# audiostick.net
KiCad netlist of a schematic drawn in EAGLE
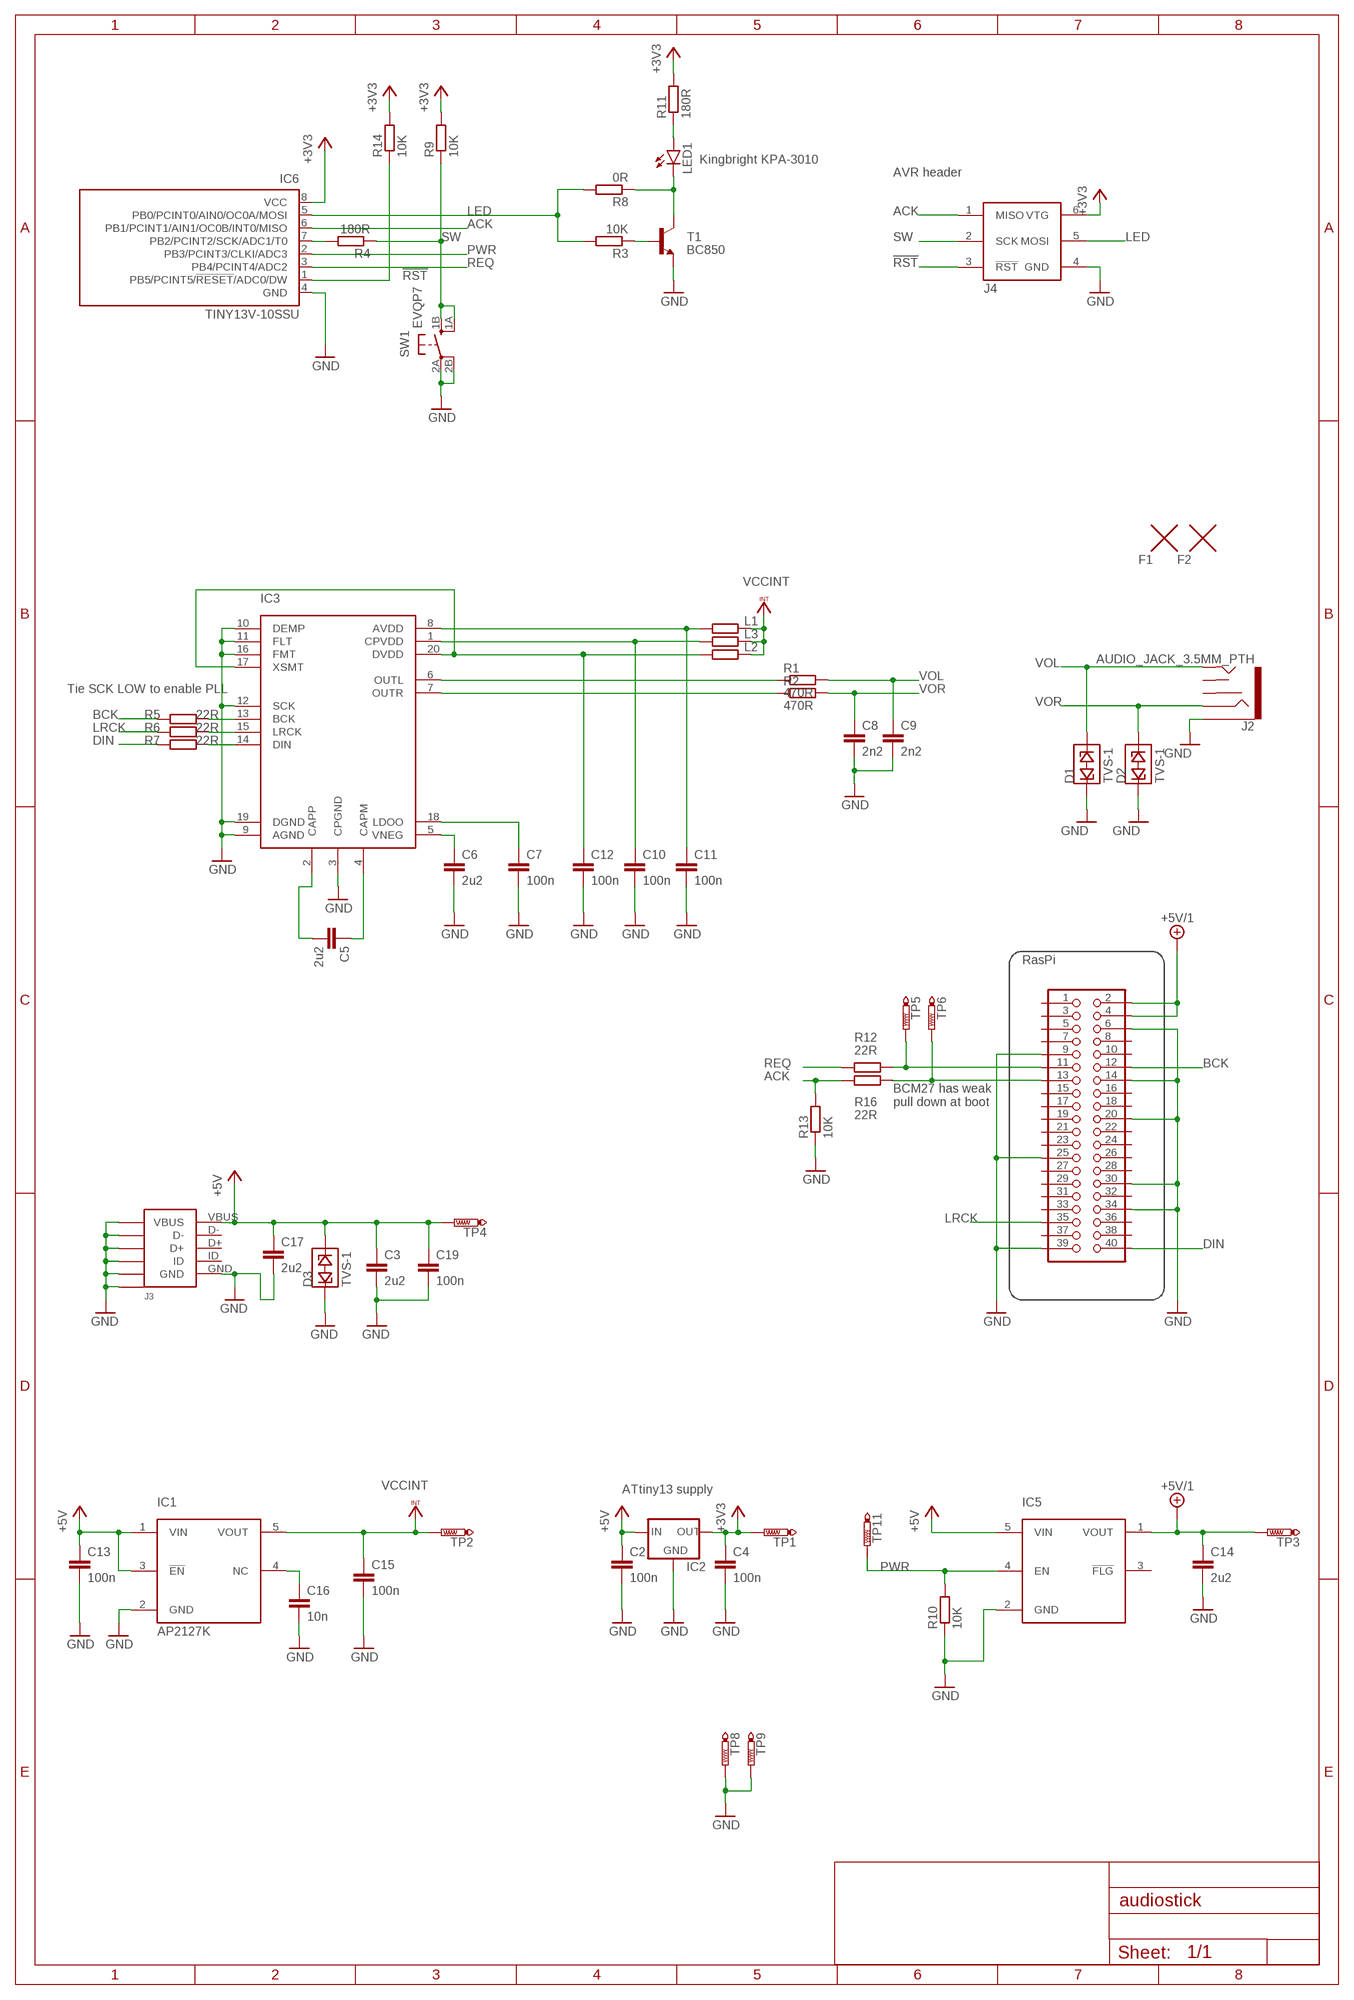
[diagram p0: schematic, sheet 1]

(export (version "E")
  (design (tool "Eeschema 10.0.6"))
  (components
    (comp (ref "C2")
      (value "100n")
      (footprint "eagle-import:C0603")
      (libsource (lib "eagle-import") (part "C-EUC0603"))
    )
    (comp (ref "C3")
      (value "2u2")
      (footprint "eagle-import:C0603")
      (libsource (lib "eagle-import") (part "C-EUC0603"))
    )
    (comp (ref "C4")
      (value "100n")
      (footprint "eagle-import:C0603")
      (libsource (lib "eagle-import") (part "C-EUC0603"))
    )
    (comp (ref "C5")
      (value "2u2")
      (footprint "eagle-import:C0603")
      (libsource (lib "eagle-import") (part "C-EUC0603"))
    )
    (comp (ref "C6")
      (value "2u2")
      (footprint "eagle-import:C0603")
      (libsource (lib "eagle-import") (part "C-EUC0603"))
    )
    (comp (ref "C7")
      (value "100n")
      (footprint "eagle-import:C0603")
      (libsource (lib "eagle-import") (part "C-EUC0603"))
    )
    (comp (ref "C8")
      (value "2n2")
      (footprint "eagle-import:C0603")
      (libsource (lib "eagle-import") (part "C-EUC0603"))
    )
    (comp (ref "C9")
      (value "2n2")
      (footprint "eagle-import:C0603")
      (libsource (lib "eagle-import") (part "C-EUC0603"))
    )
    (comp (ref "C10")
      (value "100n")
      (footprint "eagle-import:C0603")
      (libsource (lib "eagle-import") (part "C-EUC0603"))
    )
    (comp (ref "C11")
      (value "100n")
      (footprint "eagle-import:C0603")
      (libsource (lib "eagle-import") (part "C-EUC0603"))
    )
    (comp (ref "C12")
      (value "100n")
      (footprint "eagle-import:C0603")
      (libsource (lib "eagle-import") (part "C-EUC0603"))
    )
    (comp (ref "C13")
      (value "100n")
      (footprint "eagle-import:C0603")
      (libsource (lib "eagle-import") (part "C-EUC0603"))
    )
    (comp (ref "C14")
      (value "2u2")
      (footprint "eagle-import:C0603")
      (libsource (lib "eagle-import") (part "C-EUC0603"))
    )
    (comp (ref "C15")
      (value "100n")
      (footprint "eagle-import:C0603")
      (libsource (lib "eagle-import") (part "C-EUC0603"))
    )
    (comp (ref "C16")
      (value "10n")
      (footprint "eagle-import:C0603")
      (libsource (lib "eagle-import") (part "C-EUC0603"))
    )
    (comp (ref "C17")
      (value "2u2")
      (footprint "eagle-import:C0603")
      (libsource (lib "eagle-import") (part "C-EUC0603"))
    )
    (comp (ref "C19")
      (value "100n")
      (footprint "eagle-import:C0603")
      (libsource (lib "eagle-import") (part "C-EUC0603"))
    )
    (comp (ref "D1")
      (value "TVS-1")
      (footprint "eagle-import:R0603")
      (libsource (lib "eagle-import") (part "TVS-1"))
    )
    (comp (ref "D2")
      (value "TVS-1")
      (footprint "eagle-import:R0603")
      (libsource (lib "eagle-import") (part "TVS-1"))
    )
    (comp (ref "D3")
      (value "TVS-1")
      (footprint "eagle-import:R0603")
      (libsource (lib "eagle-import") (part "TVS-1"))
    )
    (comp (ref "F1")
      (value "FIDUCIALC2")
      (footprint "eagle-import:CIRCLE-1MM-3R")
      (libsource (lib "eagle-import") (part "FIDUCIALC2"))
    )
    (comp (ref "F2")
      (value "FIDUCIALC2")
      (footprint "eagle-import:CIRCLE-1MM-3R")
      (libsource (lib "eagle-import") (part "FIDUCIALC2"))
    )
    (comp (ref "IC1")
      (value "AP2127K")
      (footprint "eagle-import:GHI_SOT23-5")
      (libsource (lib "eagle-import") (part "AP2127K"))
    )
    (comp (ref "IC2")
      (value "MCP1700TT")
      (footprint "eagle-import:SOT-23")
      (libsource (lib "eagle-import") (part "MCP1700TT"))
    )
    (comp (ref "IC3")
      (value "PCM5102ASW")
      (footprint "eagle-import:TSSOP20")
      (libsource (lib "eagle-import") (part "PCM5102ASW"))
    )
    (comp (ref "IC5")
      (value "AP22804W5")
      (footprint "eagle-import:GHI_SOT23-5")
      (libsource (lib "eagle-import") (part "AP22804W5"))
    )
    (comp (ref "IC6")
      (value "TINY13V-10SSU")
      (footprint "eagle-import:8S1")
      (fields (field (name "MPN") "ATTINY13V-10SSU"))
      (libsource (lib "eagle-import") (part "TINY13SSUV-10"))
    )
    (comp (ref "J2")
      (value "AUDIO_JACK_3.5MM_PTH")
      (footprint "eagle-import:AUDIO-JACK")
      (libsource (lib "eagle-import") (part "AUDIO_JACK_3.5MM_PTH"))
    )
    (comp (ref "J3")
      (value "USB-B")
      (footprint "eagle-import:1050170001")
      (libsource (lib "eagle-import") (part "USB-B"))
    )
    (comp (ref "J4")
      (value "AVRISP")
      (footprint "eagle-import:2X3-1.27")
      (libsource (lib "eagle-import") (part "AVRISP"))
    )
    (comp (ref "L1")
      (value "F")
      (footprint "eagle-import:R0603")
      (libsource (lib "eagle-import") (part "R-EU_R0603"))
    )
    (comp (ref "L2")
      (value "F")
      (footprint "eagle-import:R0603")
      (libsource (lib "eagle-import") (part "R-EU_R0603"))
    )
    (comp (ref "L3")
      (value "F")
      (footprint "eagle-import:R0603")
      (libsource (lib "eagle-import") (part "R-EU_R0603"))
    )
    (comp (ref "LED1")
      (value "LEDLED")
      (footprint "eagle-import:KPA-3010")
      (libsource (lib "eagle-import") (part "LEDLED"))
    )
    (comp (ref "R1")
      (value "470R")
      (footprint "eagle-import:R0603")
      (libsource (lib "eagle-import") (part "R-EU_R0603"))
    )
    (comp (ref "R2")
      (value "470R")
      (footprint "eagle-import:R0603")
      (libsource (lib "eagle-import") (part "R-EU_R0603"))
    )
    (comp (ref "R3")
      (value "10K")
      (footprint "eagle-import:R0603")
      (libsource (lib "eagle-import") (part "R-EU_R0603"))
    )
    (comp (ref "R4")
      (value "180R")
      (footprint "eagle-import:R0603")
      (libsource (lib "eagle-import") (part "R-EU_R0603"))
    )
    (comp (ref "R5")
      (value "22R")
      (footprint "eagle-import:R0603")
      (libsource (lib "eagle-import") (part "R-EU_R0603"))
    )
    (comp (ref "R6")
      (value "22R")
      (footprint "eagle-import:R0603")
      (libsource (lib "eagle-import") (part "R-EU_R0603"))
    )
    (comp (ref "R7")
      (value "22R")
      (footprint "eagle-import:R0603")
      (libsource (lib "eagle-import") (part "R-EU_R0603"))
    )
    (comp (ref "R8")
      (value "0R")
      (footprint "eagle-import:R0603")
      (libsource (lib "eagle-import") (part "R-EU_R0603"))
    )
    (comp (ref "R9")
      (value "10K")
      (footprint "eagle-import:R0603")
      (libsource (lib "eagle-import") (part "R-EU_R0603"))
    )
    (comp (ref "R10")
      (value "10K")
      (footprint "eagle-import:R0603")
      (libsource (lib "eagle-import") (part "R-EU_R0603"))
    )
    (comp (ref "R11")
      (value "180R")
      (footprint "eagle-import:R0603")
      (libsource (lib "eagle-import") (part "R-EU_R0603"))
    )
    (comp (ref "R12")
      (value "22R")
      (footprint "eagle-import:R0603")
      (libsource (lib "eagle-import") (part "R-EU_R0603"))
    )
    (comp (ref "R13")
      (value "10K")
      (footprint "eagle-import:R0603")
      (libsource (lib "eagle-import") (part "R-EU_R0603"))
    )
    (comp (ref "R14")
      (value "10K")
      (footprint "eagle-import:R0603")
      (libsource (lib "eagle-import") (part "R-EU_R0603"))
    )
    (comp (ref "R16")
      (value "22R")
      (footprint "eagle-import:R0603")
      (libsource (lib "eagle-import") (part "R-EU_R0603"))
    )
    (comp (ref "SW1")
      (value "EVQP7")
      (footprint "eagle-import:EVQP7L")
      (libsource (lib "eagle-import") (part "EVQP7"))
    )
    (comp (ref "T1")
      (value "BC850")
      (footprint "eagle-import:SOT23")
      (libsource (lib "eagle-import") (part "BC850"))
    )
    (comp (ref "TP1")
      (value "PTR1PAD1-13")
      (footprint "eagle-import:P1-13")
      (libsource (lib "eagle-import") (part "PTR1PAD1-13"))
    )
    (comp (ref "TP2")
      (value "PTR1PAD1-13")
      (footprint "eagle-import:P1-13")
      (libsource (lib "eagle-import") (part "PTR1PAD1-13"))
    )
    (comp (ref "TP3")
      (value "PTR1PAD1-13")
      (footprint "eagle-import:P1-13")
      (libsource (lib "eagle-import") (part "PTR1PAD1-13"))
    )
    (comp (ref "TP4")
      (value "PTR1PAD1-13")
      (footprint "eagle-import:P1-13")
      (libsource (lib "eagle-import") (part "PTR1PAD1-13"))
    )
    (comp (ref "TP5")
      (value "PTR1PAD1-13")
      (footprint "eagle-import:P1-13")
      (libsource (lib "eagle-import") (part "PTR1PAD1-13"))
    )
    (comp (ref "TP6")
      (value "PTR1PAD1-13")
      (footprint "eagle-import:P1-13")
      (libsource (lib "eagle-import") (part "PTR1PAD1-13"))
    )
    (comp (ref "TP8")
      (value "PTR1PAD1-13")
      (footprint "eagle-import:P1-13")
      (libsource (lib "eagle-import") (part "PTR1PAD1-13"))
    )
    (comp (ref "TP9")
      (value "PTR1PAD1-13")
      (footprint "eagle-import:P1-13")
      (libsource (lib "eagle-import") (part "PTR1PAD1-13"))
    )
    (comp (ref "TP11")
      (value "PTR1PAD1-13")
      (footprint "eagle-import:P1-13")
      (libsource (lib "eagle-import") (part "PTR1PAD1-13"))
    )
    (comp (ref "U$1")
      (value "RASPIZERO")
      (footprint "eagle-import:RASPIZERO")
      (libsource (lib "eagle-import") (part "RASPIZERO"))
    )
  )
  (nets
    (net (code "1") (name "+3V3") (class "Default")
      (node (ref "C4") (pin "1") (pinfunction "1_1") (pintype "passive"))
      (node (ref "IC2") (pin "2") (pinfunction "OUT_2") (pintype "passive"))
      (node (ref "IC6") (pin "8") (pinfunction "VCC_8") (pintype "power_in"))
      (node (ref "J4") (pin "6") (pinfunction "VTG_6") (pintype "bidirectional"))
      (node (ref "R11") (pin "2") (pinfunction "2_2") (pintype "passive"))
      (node (ref "R14") (pin "2") (pinfunction "2_2") (pintype "passive"))
      (node (ref "R9") (pin "2") (pinfunction "2_2") (pintype "passive"))
      (node (ref "TP1") (pin "TP") (pinfunction "TP_TP") (pintype "input"))
    )
    (net (code "2") (name "+5V") (class "Default")
      (node (ref "C13") (pin "1") (pinfunction "1_1") (pintype "passive"))
      (node (ref "C17") (pin "1") (pinfunction "1_1") (pintype "passive"))
      (node (ref "C19") (pin "1") (pinfunction "1_1") (pintype "passive"))
      (node (ref "C2") (pin "1") (pinfunction "1_1") (pintype "passive"))
      (node (ref "C3") (pin "1") (pinfunction "1_1") (pintype "passive"))
      (node (ref "D3") (pin "2") (pinfunction "3_2") (pintype "passive"))
      (node (ref "IC1") (pin "1") (pinfunction "VIN_1") (pintype "power_in"))
      (node (ref "IC1") (pin "3") (pinfunction "~{EN}_3") (pintype "input"))
      (node (ref "IC2") (pin "3") (pinfunction "IN_3") (pintype "input"))
      (node (ref "IC5") (pin "5") (pinfunction "VIN_5") (pintype "power_in"))
      (node (ref "J3") (pin "VBUS") (pinfunction "VBUS_VBUS") (pintype "power_in"))
      (node (ref "TP4") (pin "TP") (pinfunction "TP_TP") (pintype "input"))
    )
    (net (code "3") (name "+5V{slash}1") (class "Default")
      (node (ref "C14") (pin "1") (pinfunction "1_1") (pintype "passive"))
      (node (ref "IC5") (pin "1") (pinfunction "VOUT_1") (pintype "power_in"))
      (node (ref "TP3") (pin "TP") (pinfunction "TP_TP") (pintype "input"))
      (node (ref "U$1") (pin "2") (pinfunction "5V_2") (pintype "passive"))
      (node (ref "U$1") (pin "4") (pinfunction "5V_4") (pintype "passive"))
    )
    (net (code "4") (name "/ACK") (class "Default")
      (node (ref "IC6") (pin "6") (pinfunction "PB1/PCINT1/AIN1/OC0B/INT0/MISO_6") (pintype "bidirectional"))
      (node (ref "J4") (pin "1") (pinfunction "MISO_1") (pintype "bidirectional"))
      (node (ref "R13") (pin "2") (pinfunction "2_2") (pintype "passive"))
      (node (ref "R16") (pin "1") (pinfunction "1_1") (pintype "passive"))
    )
    (net (code "5") (name "/BCK") (class "Default")
      (node (ref "R5") (pin "1") (pinfunction "1_1") (pintype "passive"))
      (node (ref "U$1") (pin "12") (pinfunction "18_12") (pintype "passive"))
    )
    (net (code "6") (name "/DIN") (class "Default")
      (node (ref "R7") (pin "1") (pinfunction "1_1") (pintype "passive"))
      (node (ref "U$1") (pin "40") (pinfunction "21_40") (pintype "passive"))
    )
    (net (code "7") (name "/LED") (class "Default")
      (node (ref "IC6") (pin "5") (pinfunction "PB0/PCINT0/AIN0/OC0A/MOSI_5") (pintype "bidirectional"))
      (node (ref "J4") (pin "5") (pinfunction "MOSI_5") (pintype "bidirectional"))
      (node (ref "R3") (pin "2") (pinfunction "2_2") (pintype "passive"))
      (node (ref "R8") (pin "2") (pinfunction "2_2") (pintype "passive"))
    )
    (net (code "8") (name "/LRCK") (class "Default")
      (node (ref "R6") (pin "1") (pinfunction "1_1") (pintype "passive"))
      (node (ref "U$1") (pin "35") (pinfunction "19_35") (pintype "passive"))
    )
    (net (code "9") (name "/PWR") (class "Default")
      (node (ref "IC5") (pin "4") (pinfunction "EN_4") (pintype "input"))
      (node (ref "IC6") (pin "2") (pinfunction "PB3/PCINT3/CLKI/ADC3_2") (pintype "bidirectional"))
      (node (ref "R10") (pin "2") (pinfunction "2_2") (pintype "passive"))
      (node (ref "TP11") (pin "TP") (pinfunction "TP_TP") (pintype "input"))
    )
    (net (code "10") (name "/REQ") (class "Default")
      (node (ref "IC6") (pin "3") (pinfunction "PB4/PCINT4/ADC2_3") (pintype "bidirectional"))
      (node (ref "R12") (pin "1") (pinfunction "1_1") (pintype "passive"))
    )
    (net (code "11") (name "/SW") (class "Default")
      (node (ref "J4") (pin "2") (pinfunction "SCK_2") (pintype "bidirectional"))
      (node (ref "R4") (pin "1") (pinfunction "1_1") (pintype "passive"))
      (node (ref "R9") (pin "1") (pinfunction "1_1") (pintype "passive"))
      (node (ref "SW1") (pin "1A") (pinfunction "S1_1A") (pintype "passive"))
      (node (ref "SW1") (pin "1B") (pinfunction "S_1B") (pintype "passive"))
    )
    (net (code "12") (name "/VOL") (class "Default")
      (node (ref "C9") (pin "1") (pinfunction "1_1") (pintype "passive"))
      (node (ref "D1") (pin "2") (pinfunction "3_2") (pintype "passive"))
      (node (ref "J2") (pin "TIP") (pinfunction "TIP_TIP") (pintype "bidirectional"))
      (node (ref "R1") (pin "2") (pinfunction "2_2") (pintype "passive"))
    )
    (net (code "13") (name "/VOR") (class "Default")
      (node (ref "C8") (pin "1") (pinfunction "1_1") (pintype "passive"))
      (node (ref "D2") (pin "2") (pinfunction "3_2") (pintype "passive"))
      (node (ref "J2") (pin "RING") (pinfunction "RING_RING") (pintype "bidirectional"))
      (node (ref "R2") (pin "2") (pinfunction "2_2") (pintype "passive"))
    )
    (net (code "14") (name "/~{RST}") (class "Default")
      (node (ref "IC6") (pin "1") (pinfunction "PB5/PCINT5/~{RESET}/ADC0/DW_1") (pintype "bidirectional"))
      (node (ref "J4") (pin "3") (pinfunction "~{RST}_3") (pintype "bidirectional"))
      (node (ref "R14") (pin "1") (pinfunction "1_1") (pintype "passive"))
    )
    (net (code "15") (name "GND") (class "Default")
      (node (ref "C10") (pin "2") (pinfunction "2_2") (pintype "passive"))
      (node (ref "C11") (pin "2") (pinfunction "2_2") (pintype "passive"))
      (node (ref "C12") (pin "2") (pinfunction "2_2") (pintype "passive"))
      (node (ref "C13") (pin "2") (pinfunction "2_2") (pintype "passive"))
      (node (ref "C14") (pin "2") (pinfunction "2_2") (pintype "passive"))
      (node (ref "C15") (pin "2") (pinfunction "2_2") (pintype "passive"))
      (node (ref "C16") (pin "2") (pinfunction "2_2") (pintype "passive"))
      (node (ref "C17") (pin "2") (pinfunction "2_2") (pintype "passive"))
      (node (ref "C19") (pin "2") (pinfunction "2_2") (pintype "passive"))
      (node (ref "C2") (pin "2") (pinfunction "2_2") (pintype "passive"))
      (node (ref "C3") (pin "2") (pinfunction "2_2") (pintype "passive"))
      (node (ref "C4") (pin "2") (pinfunction "2_2") (pintype "passive"))
      (node (ref "C6") (pin "2") (pinfunction "2_2") (pintype "passive"))
      (node (ref "C7") (pin "2") (pinfunction "2_2") (pintype "passive"))
      (node (ref "C8") (pin "2") (pinfunction "2_2") (pintype "passive"))
      (node (ref "C9") (pin "2") (pinfunction "2_2") (pintype "passive"))
      (node (ref "D1") (pin "1") (pinfunction "1_1") (pintype "passive"))
      (node (ref "D2") (pin "1") (pinfunction "1_1") (pintype "passive"))
      (node (ref "D3") (pin "1") (pinfunction "1_1") (pintype "passive"))
      (node (ref "IC1") (pin "2") (pinfunction "GND_2") (pintype "power_in"))
      (node (ref "IC2") (pin "1") (pinfunction "GND_1") (pintype "input"))
      (node (ref "IC3") (pin "10") (pinfunction "DEMP_10") (pintype "input"))
      (node (ref "IC3") (pin "11") (pinfunction "FLT_11") (pintype "input"))
      (node (ref "IC3") (pin "12") (pinfunction "SCK_12") (pintype "input"))
      (node (ref "IC3") (pin "16") (pinfunction "FMT_16") (pintype "input"))
      (node (ref "IC3") (pin "19") (pinfunction "DGND_19") (pintype "power_in"))
      (node (ref "IC3") (pin "3") (pinfunction "CPGND_3") (pintype "output"))
      (node (ref "IC3") (pin "9") (pinfunction "AGND_9") (pintype "power_in"))
      (node (ref "IC5") (pin "2") (pinfunction "GND_2") (pintype "power_in"))
      (node (ref "IC6") (pin "4") (pinfunction "GND_4") (pintype "power_in"))
      (node (ref "J2") (pin "SLEEVE") (pinfunction "SLEEVE_SLEEVE") (pintype "bidirectional"))
      (node (ref "J3") (pin "GND") (pinfunction "GND_GND") (pintype "power_in"))
      (node (ref "J3") (pin "P$1") (pinfunction "SH1*4_P$1") (pintype "power_in"))
      (node (ref "J3") (pin "P$10") (pinfunction "SH1*5_P$10") (pintype "power_in"))
      (node (ref "J3") (pin "P$11") (pinfunction "SH1*6_P$11") (pintype "power_in"))
      (node (ref "J3") (pin "P$2") (pinfunction "SH1*1_P$2") (pintype "power_in"))
      (node (ref "J3") (pin "P$3") (pinfunction "SH1*2_P$3") (pintype "power_in"))
      (node (ref "J3") (pin "P$4") (pinfunction "SH1*3_P$4") (pintype "power_in"))
      (node (ref "J4") (pin "4") (pinfunction "GND_4") (pintype "bidirectional"))
      (node (ref "R10") (pin "1") (pinfunction "1_1") (pintype "passive"))
      (node (ref "R13") (pin "1") (pinfunction "1_1") (pintype "passive"))
      (node (ref "SW1") (pin "2A") (pinfunction "P_2A") (pintype "passive"))
      (node (ref "SW1") (pin "2B") (pinfunction "P1_2B") (pintype "passive"))
      (node (ref "T1") (pin "2") (pinfunction "E_2") (pintype "passive"))
      (node (ref "TP8") (pin "TP") (pinfunction "TP_TP") (pintype "input"))
      (node (ref "TP9") (pin "TP") (pinfunction "TP_TP") (pintype "input"))
      (node (ref "U$1") (pin "14") (pinfunction "GND_14") (pintype "passive"))
      (node (ref "U$1") (pin "20") (pinfunction "GND_20") (pintype "passive"))
      (node (ref "U$1") (pin "25") (pinfunction "GND_25") (pintype "passive"))
      (node (ref "U$1") (pin "30") (pinfunction "GND_30") (pintype "passive"))
      (node (ref "U$1") (pin "34") (pinfunction "GND_34") (pintype "passive"))
      (node (ref "U$1") (pin "39") (pinfunction "GND_39") (pintype "passive"))
      (node (ref "U$1") (pin "6") (pinfunction "GND_6") (pintype "passive"))
      (node (ref "U$1") (pin "9") (pinfunction "GND_9") (pintype "passive"))
    )
    (net (code "16") (name "Net-(IC1-NC)") (class "Default")
      (node (ref "C16") (pin "1") (pinfunction "1_1") (pintype "passive"))
      (node (ref "IC1") (pin "4") (pinfunction "NC_4") (pintype "passive"))
    )
    (net (code "17") (name "Net-(IC3-AVDD)") (class "Default")
      (node (ref "C11") (pin "1") (pinfunction "1_1") (pintype "passive"))
      (node (ref "IC3") (pin "8") (pinfunction "AVDD_8") (pintype "power_in"))
      (node (ref "L1") (pin "1") (pinfunction "1_1") (pintype "passive"))
    )
    (net (code "18") (name "Net-(IC3-BCK)") (class "Default")
      (node (ref "IC3") (pin "13") (pinfunction "BCK_13") (pintype "input"))
      (node (ref "R5") (pin "2") (pinfunction "2_2") (pintype "passive"))
    )
    (net (code "19") (name "Net-(IC3-CAPM)") (class "Default")
      (node (ref "C5") (pin "1") (pinfunction "1_1") (pintype "passive"))
      (node (ref "IC3") (pin "4") (pinfunction "CAPM_4") (pintype "output"))
    )
    (net (code "20") (name "Net-(IC3-CAPP)") (class "Default")
      (node (ref "C5") (pin "2") (pinfunction "2_2") (pintype "passive"))
      (node (ref "IC3") (pin "2") (pinfunction "CAPP_2") (pintype "output"))
    )
    (net (code "21") (name "Net-(IC3-CPVDD)") (class "Default")
      (node (ref "C10") (pin "1") (pinfunction "1_1") (pintype "passive"))
      (node (ref "IC3") (pin "1") (pinfunction "CPVDD_1") (pintype "power_in"))
      (node (ref "L3") (pin "1") (pinfunction "1_1") (pintype "passive"))
    )
    (net (code "22") (name "Net-(IC3-DIN)") (class "Default")
      (node (ref "IC3") (pin "14") (pinfunction "DIN_14") (pintype "input"))
      (node (ref "R7") (pin "2") (pinfunction "2_2") (pintype "passive"))
    )
    (net (code "23") (name "Net-(IC3-DVDD)") (class "Default")
      (node (ref "C12") (pin "1") (pinfunction "1_1") (pintype "passive"))
      (node (ref "IC3") (pin "17") (pinfunction "XSMT_17") (pintype "input"))
      (node (ref "IC3") (pin "20") (pinfunction "DVDD_20") (pintype "power_in"))
      (node (ref "L2") (pin "1") (pinfunction "1_1") (pintype "passive"))
    )
    (net (code "24") (name "Net-(IC3-LDOO)") (class "Default")
      (node (ref "C7") (pin "1") (pinfunction "1_1") (pintype "passive"))
      (node (ref "IC3") (pin "18") (pinfunction "LDOO_18") (pintype "power_in"))
    )
    (net (code "25") (name "Net-(IC3-LRCK)") (class "Default")
      (node (ref "IC3") (pin "15") (pinfunction "LRCK_15") (pintype "input"))
      (node (ref "R6") (pin "2") (pinfunction "2_2") (pintype "passive"))
    )
    (net (code "26") (name "Net-(IC3-OUTL)") (class "Default")
      (node (ref "IC3") (pin "6") (pinfunction "OUTL_6") (pintype "output"))
      (node (ref "R1") (pin "1") (pinfunction "1_1") (pintype "passive"))
    )
    (net (code "27") (name "Net-(IC3-OUTR)") (class "Default")
      (node (ref "IC3") (pin "7") (pinfunction "OUTR_7") (pintype "output"))
      (node (ref "R2") (pin "1") (pinfunction "1_1") (pintype "passive"))
    )
    (net (code "28") (name "Net-(IC3-VNEG)") (class "Default")
      (node (ref "C6") (pin "1") (pinfunction "1_1") (pintype "passive"))
      (node (ref "IC3") (pin "5") (pinfunction "VNEG_5") (pintype "power_in"))
    )
    (net (code "29") (name "Net-(IC6-PB2{slash}PCINT2{slash}SCK{slash}ADC1{slash}T0)") (class "Default")
      (node (ref "IC6") (pin "7") (pinfunction "PB2/PCINT2/SCK/ADC1/T0_7") (pintype "bidirectional"))
      (node (ref "R4") (pin "2") (pinfunction "2_2") (pintype "passive"))
    )
    (net (code "30") (name "Net-(LED1-PadA)") (class "Default")
      (node (ref "LED1") (pin "A") (pinfunction "A_A") (pintype "passive"))
      (node (ref "R11") (pin "1") (pinfunction "1_1") (pintype "passive"))
    )
    (net (code "31") (name "Net-(T1-B)") (class "Default")
      (node (ref "R3") (pin "1") (pinfunction "1_1") (pintype "passive"))
      (node (ref "T1") (pin "1") (pinfunction "B_1") (pintype "passive"))
    )
    (net (code "32") (name "Net-(T1-C)") (class "Default")
      (node (ref "LED1") (pin "C") (pinfunction "C_C") (pintype "passive"))
      (node (ref "R8") (pin "1") (pinfunction "1_1") (pintype "passive"))
      (node (ref "T1") (pin "3") (pinfunction "C_3") (pintype "passive"))
    )
    (net (code "33") (name "Net-(U$1-17)") (class "Default")
      (node (ref "R12") (pin "2") (pinfunction "2_2") (pintype "passive"))
      (node (ref "TP5") (pin "TP") (pinfunction "TP_TP") (pintype "input"))
      (node (ref "U$1") (pin "11") (pinfunction "17_11") (pintype "passive"))
    )
    (net (code "34") (name "Net-(U$1-27)") (class "Default")
      (node (ref "R16") (pin "2") (pinfunction "2_2") (pintype "passive"))
      (node (ref "TP6") (pin "TP") (pinfunction "TP_TP") (pintype "input"))
      (node (ref "U$1") (pin "13") (pinfunction "27_13") (pintype "passive"))
    )
    (net (code "35") (name "VCCINT") (class "Default")
      (node (ref "C15") (pin "1") (pinfunction "1_1") (pintype "passive"))
      (node (ref "IC1") (pin "5") (pinfunction "VOUT_5") (pintype "power_in"))
      (node (ref "L1") (pin "2") (pinfunction "2_2") (pintype "passive"))
      (node (ref "L2") (pin "2") (pinfunction "2_2") (pintype "passive"))
      (node (ref "L3") (pin "2") (pinfunction "2_2") (pintype "passive"))
      (node (ref "TP2") (pin "TP") (pinfunction "TP_TP") (pintype "input"))
    )
    (net (code "36") (name "unconnected-(IC5-~{FLG}-Pad3)") (class "Default")
      (node (ref "IC5") (pin "3") (pinfunction "~{FLG}_3") (pintype "open_collector"))
    )
    (net (code "37") (name "unconnected-(J2-PadRSH)") (class "Default")
      (node (ref "J2") (pin "RSH") (pinfunction "RSH_RSH") (pintype "bidirectional"))
    )
    (net (code "38") (name "unconnected-(J2-PadTSH)") (class "Default")
      (node (ref "J2") (pin "TSH") (pinfunction "TSH_TSH") (pintype "bidirectional"))
    )
    (net (code "39") (name "unconnected-(J3-PadD+)") (class "Default")
      (node (ref "J3") (pin "D+") (pinfunction "D+_D+") (pintype "bidirectional"))
    )
    (net (code "40") (name "unconnected-(J3-PadD-)") (class "Default")
      (node (ref "J3") (pin "D-") (pinfunction "D-_D-") (pintype "bidirectional"))
    )
    (net (code "41") (name "unconnected-(J3-PadID)") (class "Default")
      (node (ref "J3") (pin "ID") (pinfunction "ID_ID") (pintype "bidirectional"))
    )
    (net (code "42") (name "unconnected-(U$1-0-Pad27)") (class "Default")
      (node (ref "U$1") (pin "27") (pinfunction "0_27") (pintype "passive"))
    )
    (net (code "43") (name "unconnected-(U$1-1-Pad28)") (class "Default")
      (node (ref "U$1") (pin "28") (pinfunction "1_28") (pintype "passive"))
    )
    (net (code "44") (name "unconnected-(U$1-2-Pad3)") (class "Default")
      (node (ref "U$1") (pin "3") (pinfunction "2_3") (pintype "passive"))
    )
    (net (code "45") (name "unconnected-(U$1-3-Pad5)") (class "Default")
      (node (ref "U$1") (pin "5") (pinfunction "3_5") (pintype "passive"))
    )
    (net (code "46") (name "unconnected-(U$1-3V3-Pad1)") (class "Default")
      (node (ref "U$1") (pin "1") (pinfunction "3V3_1") (pintype "passive"))
    )
    (net (code "47") (name "unconnected-(U$1-3V3-Pad17)") (class "Default")
      (node (ref "U$1") (pin "17") (pinfunction "3V3_17") (pintype "passive"))
    )
    (net (code "48") (name "unconnected-(U$1-4-Pad7)") (class "Default")
      (node (ref "U$1") (pin "7") (pinfunction "4_7") (pintype "passive"))
    )
    (net (code "49") (name "unconnected-(U$1-5-Pad29)") (class "Default")
      (node (ref "U$1") (pin "29") (pinfunction "5_29") (pintype "passive"))
    )
    (net (code "50") (name "unconnected-(U$1-6-Pad31)") (class "Default")
      (node (ref "U$1") (pin "31") (pinfunction "6_31") (pintype "passive"))
    )
    (net (code "51") (name "unconnected-(U$1-7-Pad26)") (class "Default")
      (node (ref "U$1") (pin "26") (pinfunction "7_26") (pintype "passive"))
    )
    (net (code "52") (name "unconnected-(U$1-8-Pad24)") (class "Default")
      (node (ref "U$1") (pin "24") (pinfunction "8_24") (pintype "passive"))
    )
    (net (code "53") (name "unconnected-(U$1-9-Pad21)") (class "Default")
      (node (ref "U$1") (pin "21") (pinfunction "9_21") (pintype "passive"))
    )
    (net (code "54") (name "unconnected-(U$1-10-Pad19)") (class "Default")
      (node (ref "U$1") (pin "19") (pinfunction "10_19") (pintype "passive"))
    )
    (net (code "55") (name "unconnected-(U$1-11-Pad23)") (class "Default")
      (node (ref "U$1") (pin "23") (pinfunction "11_23") (pintype "passive"))
    )
    (net (code "56") (name "unconnected-(U$1-12-Pad32)") (class "Default")
      (node (ref "U$1") (pin "32") (pinfunction "12_32") (pintype "passive"))
    )
    (net (code "57") (name "unconnected-(U$1-13-Pad33)") (class "Default")
      (node (ref "U$1") (pin "33") (pinfunction "13_33") (pintype "passive"))
    )
    (net (code "58") (name "unconnected-(U$1-14-Pad8)") (class "Default")
      (node (ref "U$1") (pin "8") (pinfunction "14_8") (pintype "passive"))
    )
    (net (code "59") (name "unconnected-(U$1-15-Pad10)") (class "Default")
      (node (ref "U$1") (pin "10") (pinfunction "15_10") (pintype "passive"))
    )
    (net (code "60") (name "unconnected-(U$1-16-Pad36)") (class "Default")
      (node (ref "U$1") (pin "36") (pinfunction "16_36") (pintype "passive"))
    )
    (net (code "61") (name "unconnected-(U$1-20-Pad38)") (class "Default")
      (node (ref "U$1") (pin "38") (pinfunction "20_38") (pintype "passive"))
    )
    (net (code "62") (name "unconnected-(U$1-22-Pad15)") (class "Default")
      (node (ref "U$1") (pin "15") (pinfunction "22_15") (pintype "passive"))
    )
    (net (code "63") (name "unconnected-(U$1-23-Pad16)") (class "Default")
      (node (ref "U$1") (pin "16") (pinfunction "23_16") (pintype "passive"))
    )
    (net (code "64") (name "unconnected-(U$1-24-Pad18)") (class "Default")
      (node (ref "U$1") (pin "18") (pinfunction "24_18") (pintype "passive"))
    )
    (net (code "65") (name "unconnected-(U$1-25-Pad22)") (class "Default")
      (node (ref "U$1") (pin "22") (pinfunction "25_22") (pintype "passive"))
    )
    (net (code "66") (name "unconnected-(U$1-26-Pad37)") (class "Default")
      (node (ref "U$1") (pin "37") (pinfunction "26_37") (pintype "passive"))
    )
  )
)
